# riffle-thpr-v0_1.net
KiCad netlist of a schematic drawn in EAGLE
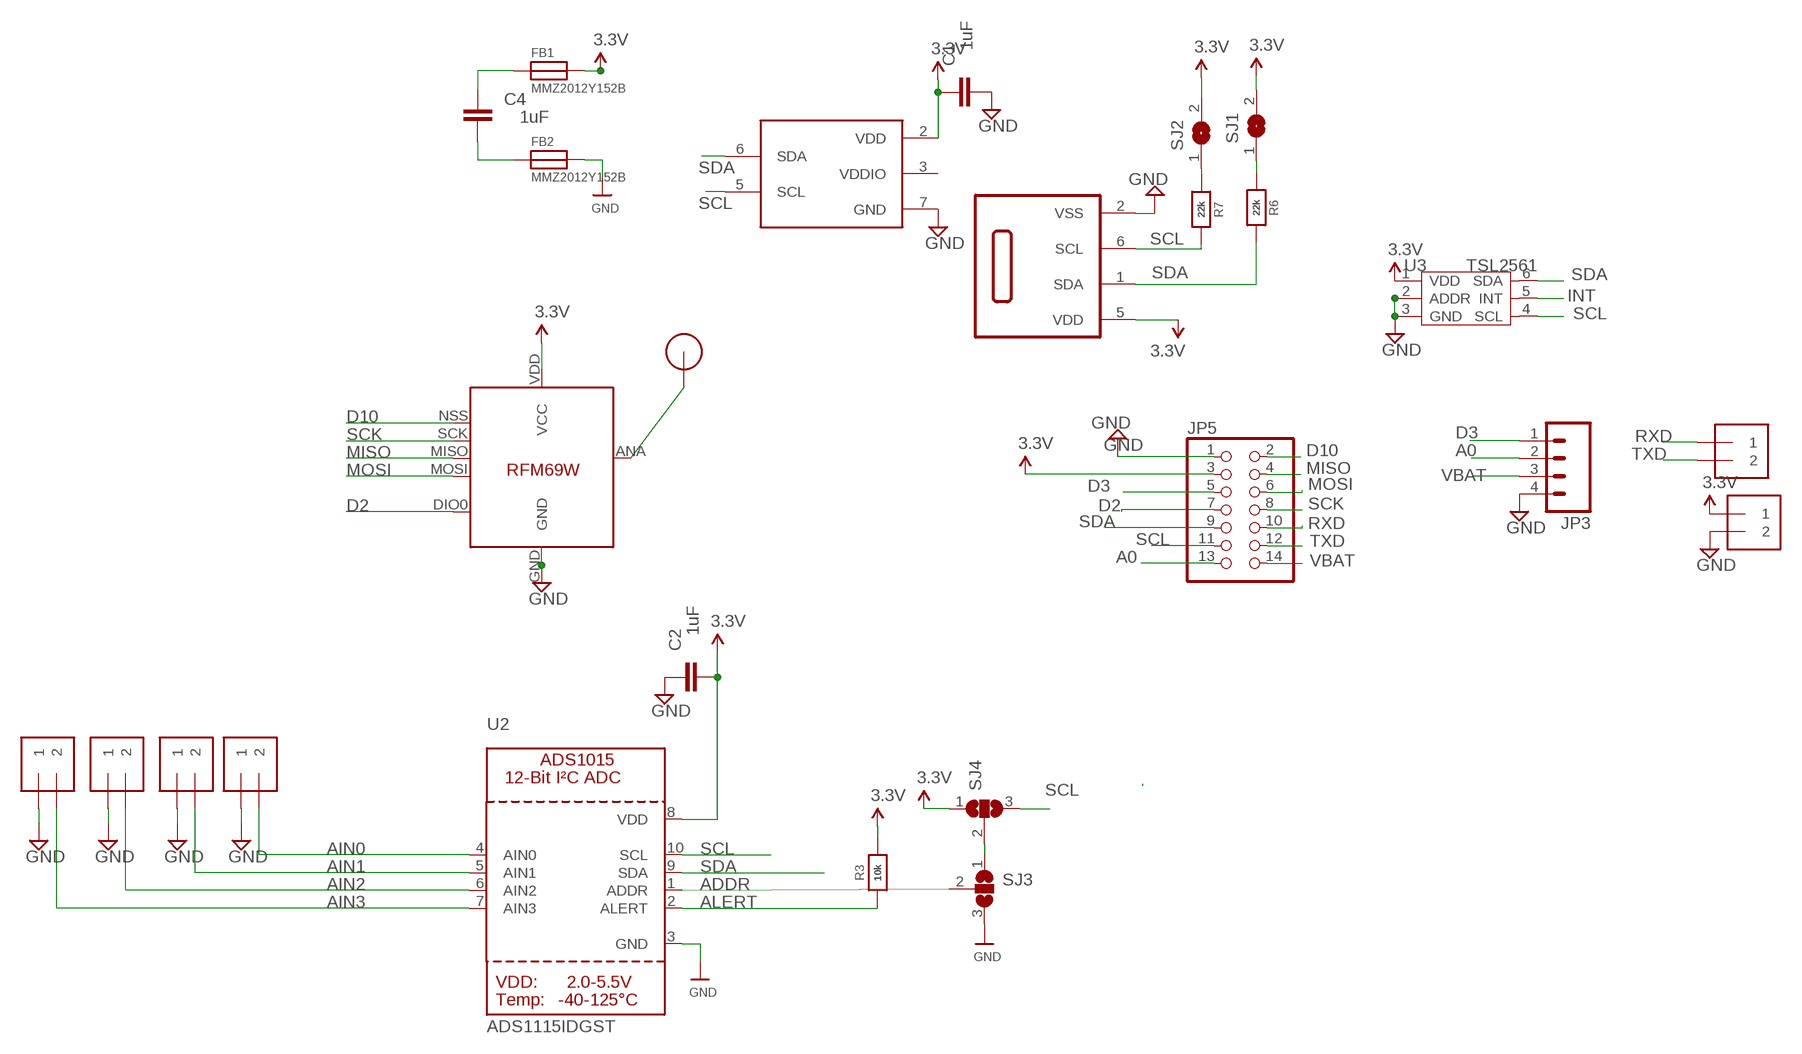
[diagram p0: schematic, sheet 1]

(export (version "E")
  (design (tool "Eeschema 10.0.6"))
  (components
    (comp (ref "C1")
      (value "1uF")
      (footprint "eagle-import:0603-CAP")
      (libsource (lib "eagle-import") (part "CAP0603-CAP"))
    )
    (comp (ref "C2")
      (value "1uF")
      (footprint "eagle-import:0603-CAP")
      (libsource (lib "eagle-import") (part "CAP0603-CAP"))
    )
    (comp (ref "C4")
      (value "1uF")
      (footprint "eagle-import:0603-CAP")
      (libsource (lib "eagle-import") (part "CAP0603-CAP"))
    )
    (comp (ref "FB1")
      (value "MMZ2012Y152B")
      (footprint "eagle-import:0805")
      (libsource (lib "eagle-import") (part "FERRITE0805"))
    )
    (comp (ref "FB2")
      (value "MMZ2012Y152B")
      (footprint "eagle-import:0805")
      (libsource (lib "eagle-import") (part "FERRITE0805"))
    )
    (comp (ref "IN0")
      (value "1X2-3.5MM")
      (footprint "eagle-import:1X2-3.5MM")
      (libsource (lib "eagle-import") (part "1X2-3.5MM"))
    )
    (comp (ref "IN1")
      (value "1X2-3.5MM")
      (footprint "eagle-import:1X2-3.5MM")
      (libsource (lib "eagle-import") (part "1X2-3.5MM"))
    )
    (comp (ref "IN2")
      (value "1X2-3.5MM")
      (footprint "eagle-import:1X2-3.5MM")
      (libsource (lib "eagle-import") (part "1X2-3.5MM"))
    )
    (comp (ref "IN3")
      (value "1X2-3.5MM")
      (footprint "eagle-import:1X2-3.5MM")
      (libsource (lib "eagle-import") (part "1X2-3.5MM"))
    )
    (comp (ref "IN4")
      (value "1X2-3.5MM")
      (footprint "eagle-import:1X2-3.5MM")
      (libsource (lib "eagle-import") (part "1X2-3.5MM"))
    )
    (comp (ref "IN5")
      (value "1X2-3.5MM")
      (footprint "eagle-import:1X2-3.5MM")
      (libsource (lib "eagle-import") (part "1X2-3.5MM"))
    )
    (comp (ref "JP3")
      (value "M04SMD")
      (footprint "eagle-import:1X04-SMD")
      (libsource (lib "eagle-import") (part "M04SMD"))
    )
    (comp (ref "JP5")
      (value "PINHD-2X7")
      (footprint "eagle-import:2X07")
      (libsource (lib "eagle-import") (part "PINHD-2X7"))
    )
    (comp (ref "R3")
      (value "10k")
      (footprint "eagle-import:0603-NO")
      (libsource (lib "eagle-import") (part "RESISTOR_0603_NOOUT"))
    )
    (comp (ref "R6")
      (value "22k")
      (footprint "eagle-import:0603-NO")
      (libsource (lib "eagle-import") (part "RESISTOR_0603_NOOUT"))
    )
    (comp (ref "R7")
      (value "22k")
      (footprint "eagle-import:0603-NO")
      (libsource (lib "eagle-import") (part "RESISTOR_0603_NOOUT"))
    )
    (comp (ref "SJ1") (value "SJ") (footprint "eagle-import:SJ") (libsource (lib "eagle-import") (part "SJ")))
    (comp (ref "SJ2") (value "SJ") (footprint "eagle-import:SJ") (libsource (lib "eagle-import") (part "SJ")))
    (comp (ref "SJ3")
      (value "SJ2W")
      (footprint "eagle-import:SJ_2")
      (libsource (lib "eagle-import") (part "SJ2W"))
    )
    (comp (ref "SJ4")
      (value "SJ2W")
      (footprint "eagle-import:SJ_2")
      (libsource (lib "eagle-import") (part "SJ2W"))
    )
    (comp (ref "SN1")
      (value "SHT21")
      (footprint "eagle-import:DFN6_SHT")
      (libsource (lib "eagle-import") (part "SHT21"))
    )
    (comp (ref "U$1")
      (value "RFM12B_ANTENNA")
      (footprint "eagle-import:RFM12B-ANTENNA")
      (libsource (lib "eagle-import") (part "RFM12B_ANTENNA"))
    )
    (comp (ref "U$5")
      (value "RFM69")
      (footprint "eagle-import:RFM69W-MINPADS")
      (libsource (lib "eagle-import") (part "RFM69"))
    )
    (comp (ref "U1")
      (value "BMP180")
      (footprint "eagle-import:BMP180")
      (libsource (lib "eagle-import") (part "BMP180"))
    )
    (comp (ref "U2")
      (value "ADS1115IDGST")
      (footprint "eagle-import:MSOP10")
      (libsource (lib "eagle-import") (part "ADC_ADS1015"))
    )
    (comp (ref "U3")
      (value "TSL2561")
      (footprint "eagle-import:TMB-6")
      (libsource (lib "eagle-import") (part "TSL2561T"))
    )
  )
  (nets
    (net (code "1") (name "/A0") (class "Default")
      (node (ref "JP3") (pin "2") (pinfunction "2_2") (pintype "passive"))
      (node (ref "JP5") (pin "13") (pinfunction "13_13") (pintype "passive"))
    )
    (net (code "2") (name "/ADDR") (class "Default")
      (node (ref "SJ3") (pin "2") (pinfunction "2_2") (pintype "passive"))
      (node (ref "U2") (pin "1") (pinfunction "ADDR_1") (pintype "bidirectional"))
    )
    (net (code "3") (name "/AIN0") (class "Default")
      (node (ref "IN0") (pin "2") (pinfunction "2_2") (pintype "passive"))
      (node (ref "U2") (pin "4") (pinfunction "AIN0_4") (pintype "bidirectional"))
    )
    (net (code "4") (name "/AIN1") (class "Default")
      (node (ref "IN1") (pin "2") (pinfunction "2_2") (pintype "passive"))
      (node (ref "U2") (pin "5") (pinfunction "AIN1_5") (pintype "bidirectional"))
    )
    (net (code "5") (name "/AIN2") (class "Default")
      (node (ref "IN2") (pin "2") (pinfunction "2_2") (pintype "passive"))
      (node (ref "U2") (pin "6") (pinfunction "AIN2_6") (pintype "bidirectional"))
    )
    (net (code "6") (name "/AIN3") (class "Default")
      (node (ref "IN3") (pin "2") (pinfunction "2_2") (pintype "passive"))
      (node (ref "U2") (pin "7") (pinfunction "AIN3_7") (pintype "bidirectional"))
    )
    (net (code "7") (name "/ALERT") (class "Default")
      (node (ref "R3") (pin "1") (pinfunction "1_1") (pintype "passive"))
      (node (ref "U2") (pin "2") (pinfunction "ALERT_2") (pintype "bidirectional"))
    )
    (net (code "8") (name "/D2") (class "Default")
      (node (ref "JP5") (pin "7") (pinfunction "7_7") (pintype "passive"))
      (node (ref "U$5") (pin "DIO0") (pinfunction "DIO0_DIO0") (pintype "open_collector"))
    )
    (net (code "9") (name "/D3") (class "Default")
      (node (ref "JP3") (pin "1") (pinfunction "1_1") (pintype "passive"))
      (node (ref "JP5") (pin "5") (pinfunction "5_5") (pintype "passive"))
    )
    (net (code "10") (name "/D10") (class "Default")
      (node (ref "JP5") (pin "2") (pinfunction "2_2") (pintype "passive"))
      (node (ref "U$5") (pin "NSS") (pinfunction "SEL_NSS") (pintype "input"))
    )
    (net (code "11") (name "/INT") (class "Default")
      (node (ref "U3") (pin "5") (pinfunction "INT_5") (pintype "output"))
    )
    (net (code "12") (name "/MISO") (class "Default")
      (node (ref "JP5") (pin "4") (pinfunction "4_4") (pintype "passive"))
      (node (ref "U$5") (pin "MISO") (pinfunction "MISO_MISO") (pintype "input"))
    )
    (net (code "13") (name "/MOSI") (class "Default")
      (node (ref "JP5") (pin "6") (pinfunction "6_6") (pintype "passive"))
      (node (ref "U$5") (pin "MOSI") (pinfunction "MOSI_MOSI") (pintype "output"))
    )
    (net (code "14") (name "/RXD") (class "Default")
      (node (ref "IN4") (pin "1") (pinfunction "1_1") (pintype "passive"))
      (node (ref "JP5") (pin "10") (pinfunction "10_10") (pintype "passive"))
    )
    (net (code "15") (name "/SCK") (class "Default")
      (node (ref "JP5") (pin "8") (pinfunction "8_8") (pintype "passive"))
      (node (ref "U$5") (pin "SCK") (pinfunction "SCK_SCK") (pintype "input"))
    )
    (net (code "16") (name "/SCL") (class "Default")
      (node (ref "JP5") (pin "11") (pinfunction "11_11") (pintype "passive"))
      (node (ref "R7") (pin "2") (pinfunction "2_2") (pintype "passive"))
      (node (ref "SJ4") (pin "3") (pinfunction "3_3") (pintype "passive"))
      (node (ref "SN1") (pin "6") (pinfunction "SCL_6") (pintype "bidirectional"))
      (node (ref "U1") (pin "5") (pinfunction "SCL_5") (pintype "input"))
      (node (ref "U2") (pin "10") (pinfunction "SCL_10") (pintype "bidirectional"))
      (node (ref "U3") (pin "4") (pinfunction "SCL_4") (pintype "input"))
    )
    (net (code "17") (name "/SDA") (class "Default")
      (node (ref "JP5") (pin "9") (pinfunction "9_9") (pintype "passive"))
      (node (ref "R6") (pin "2") (pinfunction "2_2") (pintype "passive"))
      (node (ref "SN1") (pin "1") (pinfunction "SDA_1") (pintype "bidirectional"))
      (node (ref "U1") (pin "6") (pinfunction "SDA_6") (pintype "bidirectional"))
      (node (ref "U2") (pin "9") (pinfunction "SDA_9") (pintype "bidirectional"))
      (node (ref "U3") (pin "6") (pinfunction "SDA_6") (pintype "bidirectional"))
    )
    (net (code "18") (name "/TXD") (class "Default")
      (node (ref "IN4") (pin "2") (pinfunction "2_2") (pintype "passive"))
      (node (ref "JP5") (pin "12") (pinfunction "12_12") (pintype "passive"))
    )
    (net (code "19") (name "/VBAT") (class "Default")
      (node (ref "JP3") (pin "3") (pinfunction "3_3") (pintype "passive"))
      (node (ref "JP5") (pin "14") (pinfunction "14_14") (pintype "passive"))
    )
    (net (code "20") (name "/VDDIO") (class "Default")
      (node (ref "U1") (pin "3") (pinfunction "VDDIO_3") (pintype "power_in"))
    )
    (net (code "21") (name "3.3V") (class "Default")
      (node (ref "C1") (pin "2") (pinfunction "2_2") (pintype "passive"))
      (node (ref "C2") (pin "1") (pinfunction "1_1") (pintype "passive"))
      (node (ref "FB1") (pin "2") (pinfunction "P$2_2") (pintype "bidirectional"))
      (node (ref "IN5") (pin "1") (pinfunction "1_1") (pintype "passive"))
      (node (ref "JP5") (pin "3") (pinfunction "3_3") (pintype "passive"))
      (node (ref "R3") (pin "2") (pinfunction "2_2") (pintype "passive"))
      (node (ref "SJ1") (pin "2") (pinfunction "2_2") (pintype "passive"))
      (node (ref "SJ2") (pin "2") (pinfunction "2_2") (pintype "passive"))
      (node (ref "SJ4") (pin "1") (pinfunction "1_1") (pintype "passive"))
      (node (ref "SN1") (pin "5") (pinfunction "VDD_5") (pintype "power_in"))
      (node (ref "U$5") (pin "VDD") (pinfunction "VCC_VDD") (pintype "power_in"))
      (node (ref "U1") (pin "2") (pinfunction "VDD_2") (pintype "power_in"))
      (node (ref "U2") (pin "8") (pinfunction "VDD_8") (pintype "bidirectional"))
      (node (ref "U3") (pin "1") (pinfunction "VDD_1") (pintype "power_in"))
    )
    (net (code "22") (name "GND") (class "Default")
      (node (ref "C1") (pin "1") (pinfunction "1_1") (pintype "passive"))
      (node (ref "C2") (pin "2") (pinfunction "2_2") (pintype "passive"))
      (node (ref "FB2") (pin "2") (pinfunction "P$2_2") (pintype "bidirectional"))
      (node (ref "IN0") (pin "1") (pinfunction "1_1") (pintype "passive"))
      (node (ref "IN1") (pin "1") (pinfunction "1_1") (pintype "passive"))
      (node (ref "IN2") (pin "1") (pinfunction "1_1") (pintype "passive"))
      (node (ref "IN3") (pin "1") (pinfunction "1_1") (pintype "passive"))
      (node (ref "IN5") (pin "2") (pinfunction "2_2") (pintype "passive"))
      (node (ref "JP3") (pin "4") (pinfunction "4_4") (pintype "passive"))
      (node (ref "JP5") (pin "1") (pinfunction "1_1") (pintype "passive"))
      (node (ref "SJ3") (pin "3") (pinfunction "3_3") (pintype "passive"))
      (node (ref "SN1") (pin "2") (pinfunction "VSS_2") (pintype "power_in"))
      (node (ref "U$5") (pin "GND") (pinfunction "GND_GND") (pintype "power_in"))
      (node (ref "U1") (pin "7") (pinfunction "GND_7") (pintype "power_in"))
      (node (ref "U2") (pin "3") (pinfunction "GND_3") (pintype "bidirectional"))
      (node (ref "U3") (pin "2") (pinfunction "ADDR_2") (pintype "input"))
      (node (ref "U3") (pin "3") (pinfunction "GND_3") (pintype "power_in"))
    )
    (net (code "23") (name "Net-(FB1-P$1)") (class "Default")
      (node (ref "C4") (pin "2") (pinfunction "2_2") (pintype "passive"))
      (node (ref "FB1") (pin "1") (pinfunction "P$1_1") (pintype "bidirectional"))
    )
    (net (code "24") (name "Net-(FB2-P$1)") (class "Default")
      (node (ref "C4") (pin "1") (pinfunction "1_1") (pintype "passive"))
      (node (ref "FB2") (pin "1") (pinfunction "P$1_1") (pintype "bidirectional"))
    )
    (net (code "25") (name "Net-(R6-Pad1)") (class "Default")
      (node (ref "R6") (pin "1") (pinfunction "1_1") (pintype "passive"))
      (node (ref "SJ1") (pin "1") (pinfunction "1_1") (pintype "passive"))
    )
    (net (code "26") (name "Net-(R7-Pad1)") (class "Default")
      (node (ref "R7") (pin "1") (pinfunction "1_1") (pintype "passive"))
      (node (ref "SJ2") (pin "1") (pinfunction "1_1") (pintype "passive"))
    )
    (net (code "27") (name "Net-(SJ3-Pad1)") (class "Default")
      (node (ref "SJ3") (pin "1") (pinfunction "1_1") (pintype "passive"))
      (node (ref "SJ4") (pin "2") (pinfunction "2_2") (pintype "passive"))
    )
    (net (code "28") (name "Net-(U$1-1)") (class "Default")
      (node (ref "U$1") (pin "P$1") (pinfunction "1_P$1") (pintype "bidirectional"))
      (node (ref "U$5") (pin "ANA") (pinfunction "ANT_ANA") (pintype "passive"))
    )
  )
)
